# 5LongConnector.net
KiCad netlist of a schematic drawn in EAGLE
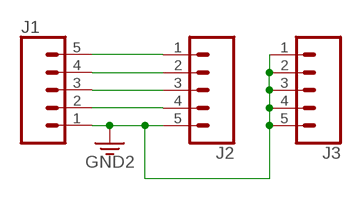
[diagram p0: schematic, sheet 1]

(export (version "E")
  (design (tool "Eeschema 10.0.6"))
  (components
    (comp (ref "J1")
      (value "CONN_05PTH_LONGPADS")
      (footprint "eagle-import:1X05_LONGPADS")
      (libsource (lib "eagle-import") (part "CONN_05PTH_LONGPADS"))
    )
    (comp (ref "J2")
      (value "CONN_05PTH_LONGPADS")
      (footprint "eagle-import:1X05_LONGPADS")
      (libsource (lib "eagle-import") (part "CONN_05PTH_LONGPADS"))
    )
    (comp (ref "J3")
      (value "CONN_05PTH_LONGPADS")
      (footprint "eagle-import:1X05_LONGPADS")
      (libsource (lib "eagle-import") (part "CONN_05PTH_LONGPADS"))
    )
  )
  (nets
    (net (code "1") (name "GND2") (class "Default")
      (node (ref "J1") (pin "1") (pinfunction "1_1") (pintype "passive"))
      (node (ref "J2") (pin "5") (pinfunction "5_5") (pintype "passive"))
      (node (ref "J3") (pin "1") (pinfunction "1_1") (pintype "passive"))
      (node (ref "J3") (pin "2") (pinfunction "2_2") (pintype "passive"))
      (node (ref "J3") (pin "3") (pinfunction "3_3") (pintype "passive"))
      (node (ref "J3") (pin "4") (pinfunction "4_4") (pintype "passive"))
      (node (ref "J3") (pin "5") (pinfunction "5_5") (pintype "passive"))
    )
    (net (code "2") (name "Net-(J1-Pad2)") (class "Default")
      (node (ref "J1") (pin "2") (pinfunction "2_2") (pintype "passive"))
      (node (ref "J2") (pin "4") (pinfunction "4_4") (pintype "passive"))
    )
    (net (code "3") (name "Net-(J1-Pad3)") (class "Default")
      (node (ref "J1") (pin "3") (pinfunction "3_3") (pintype "passive"))
      (node (ref "J2") (pin "3") (pinfunction "3_3") (pintype "passive"))
    )
    (net (code "4") (name "Net-(J1-Pad4)") (class "Default")
      (node (ref "J1") (pin "4") (pinfunction "4_4") (pintype "passive"))
      (node (ref "J2") (pin "2") (pinfunction "2_2") (pintype "passive"))
    )
    (net (code "5") (name "Net-(J1-Pad5)") (class "Default")
      (node (ref "J1") (pin "5") (pinfunction "5_5") (pintype "passive"))
      (node (ref "J2") (pin "1") (pinfunction "1_1") (pintype "passive"))
    )
  )
)
